# alimentare_no_ac.net
KiCad netlist of a schematic drawn in EAGLE
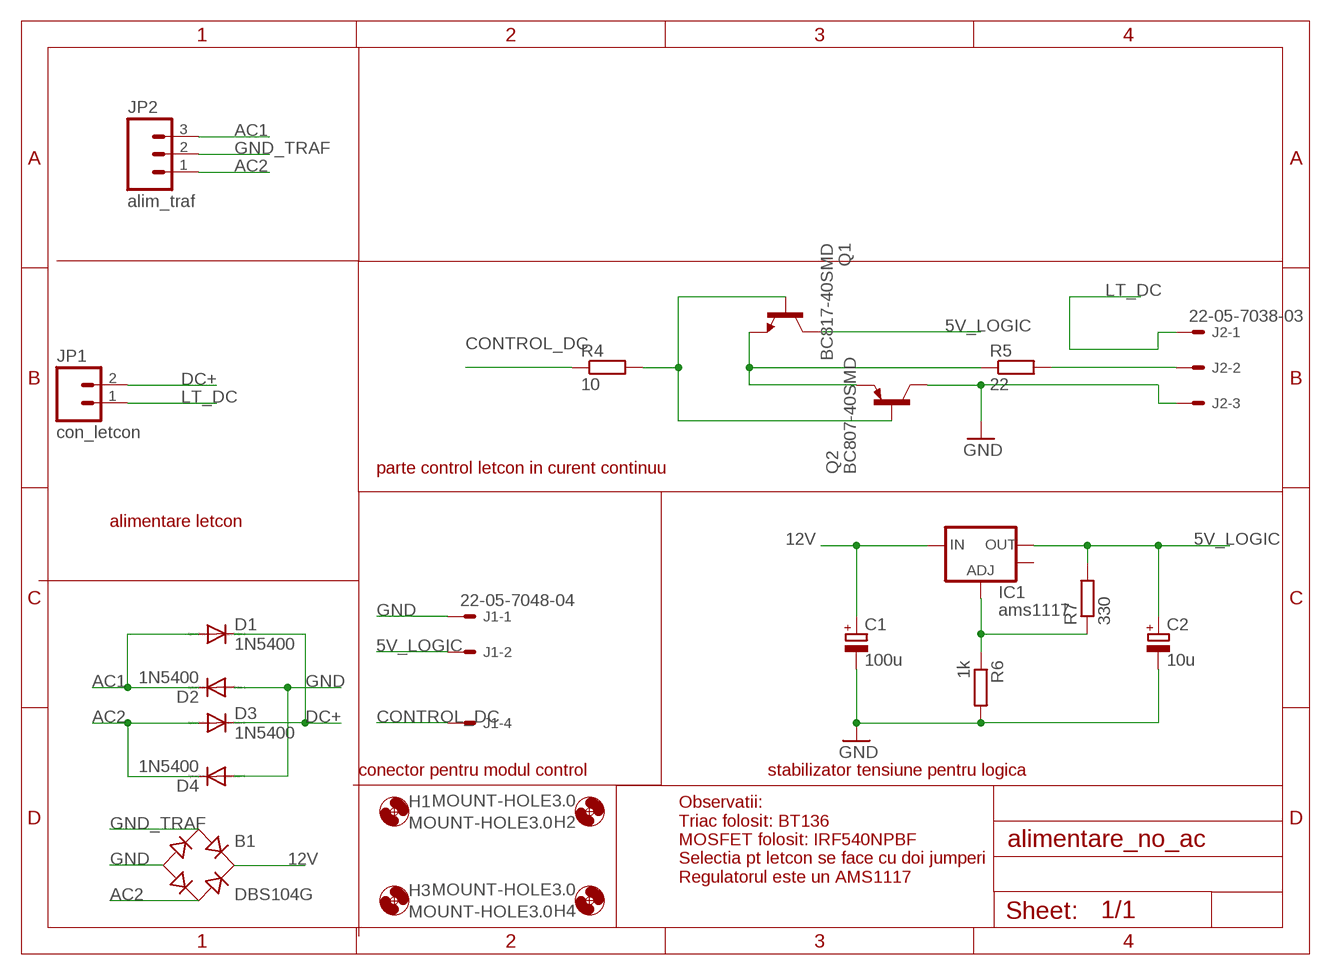
[diagram p0: schematic, sheet 1]

(export (version "E")
  (design (tool "Eeschema 10.0.6"))
  (components
    (comp (ref "B1")
      (value "DBS104G")
      (footprint "eagle-import:DBS")
      (libsource (lib "eagle-import") (part "DB?GS104"))
    )
    (comp (ref "C1")
      (value "100u")
      (footprint "eagle-import:E2,5-6E")
      (libsource (lib "eagle-import") (part "CPOL-EUE2,5-6E"))
    )
    (comp (ref "C2")
      (value "10u")
      (footprint "eagle-import:E2,5-6E")
      (libsource (lib "eagle-import") (part "CPOL-EUE2,5-6E"))
    )
    (comp (ref "D1")
      (value "1N5400")
      (footprint "eagle-import:DO201-15")
      (libsource (lib "eagle-import") (part "1N5400"))
    )
    (comp (ref "D2")
      (value "1N5400")
      (footprint "eagle-import:DO201-15")
      (libsource (lib "eagle-import") (part "1N5400"))
    )
    (comp (ref "D3")
      (value "1N5400")
      (footprint "eagle-import:DO201-15")
      (libsource (lib "eagle-import") (part "1N5400"))
    )
    (comp (ref "D4")
      (value "1N5400")
      (footprint "eagle-import:DO201-15")
      (libsource (lib "eagle-import") (part "1N5400"))
    )
    (comp (ref "H1")
      (value "MOUNT-HOLE3.0")
      (footprint "eagle-import:3,0")
      (libsource (lib "eagle-import") (part "MOUNT-HOLE3.0"))
    )
    (comp (ref "H2")
      (value "MOUNT-HOLE3.0")
      (footprint "eagle-import:3,0")
      (libsource (lib "eagle-import") (part "MOUNT-HOLE3.0"))
    )
    (comp (ref "H3")
      (value "MOUNT-HOLE3.0")
      (footprint "eagle-import:3,0")
      (libsource (lib "eagle-import") (part "MOUNT-HOLE3.0"))
    )
    (comp (ref "H4")
      (value "MOUNT-HOLE3.0")
      (footprint "eagle-import:3,0")
      (libsource (lib "eagle-import") (part "MOUNT-HOLE3.0"))
    )
    (comp (ref "IC1")
      (value "ams1117")
      (footprint "eagle-import:SOT223")
      (libsource (lib "eagle-import") (part "V_REG_LM1117SOT223"))
    )
    (comp (ref "J1")
      (value "22-05-7048-04")
      (footprint "eagle-import:7395-04")
      (libsource (lib "eagle-import") (part "22-?-0405-7048"))
    )
    (comp (ref "J2")
      (value "22-05-7038-03")
      (footprint "eagle-import:7395-03")
      (libsource (lib "eagle-import") (part "22-?-0305-7038"))
    )
    (comp (ref "JP1")
      (value "con_letcon")
      (footprint "eagle-import:SCREWTERMINAL-3.5MM-2")
      (libsource (lib "eagle-import") (part "M023.5MM"))
    )
    (comp (ref "JP2")
      (value "alim_traf")
      (footprint "eagle-import:SCREWTERMINAL-3.5MM-3")
      (libsource (lib "eagle-import") (part "M03SCREW"))
    )
    (comp (ref "Q1")
      (value "BC817-40SMD")
      (footprint "eagle-import:SOT23-BEC")
      (libsource (lib "eagle-import") (part "BC817SMD-40"))
    )
    (comp (ref "Q2")
      (value "BC807-40SMD")
      (footprint "eagle-import:SOT23-BEC")
      (libsource (lib "eagle-import") (part "BC807SMD-40"))
    )
    (comp (ref "R4")
      (value "10")
      (footprint "eagle-import:M1206")
      (libsource (lib "eagle-import") (part "R-EU_M1206"))
    )
    (comp (ref "R5")
      (value "22")
      (footprint "eagle-import:M1206")
      (libsource (lib "eagle-import") (part "R-EU_M1206"))
    )
    (comp (ref "R6")
      (value "1k")
      (footprint "eagle-import:M1206")
      (libsource (lib "eagle-import") (part "R-EU_M1206"))
    )
    (comp (ref "R7")
      (value "330")
      (footprint "eagle-import:M1206")
      (libsource (lib "eagle-import") (part "R-EU_M1206"))
    )
  )
  (nets
    (net (code "1") (name "/5V_LOGIC") (class "Default")
      (node (ref "C2") (pin "+") (pinfunction "+_+") (pintype "passive"))
      (node (ref "IC1") (pin "2") (pinfunction "OUT_2") (pintype "output"))
      (node (ref "J1") (pin "2") (pinfunction "S_2") (pintype "passive"))
      (node (ref "Q1") (pin "C") (pinfunction "C_C") (pintype "passive"))
      (node (ref "R7") (pin "2") (pinfunction "2_2") (pintype "passive"))
    )
    (net (code "2") (name "/12V") (class "Default")
      (node (ref "B1") (pin "+") (pinfunction "+_+") (pintype "passive"))
      (node (ref "C1") (pin "+") (pinfunction "+_+") (pintype "passive"))
      (node (ref "IC1") (pin "3") (pinfunction "IN_3") (pintype "input"))
    )
    (net (code "3") (name "/AC1") (class "Default")
      (node (ref "D1") (pin "A") (pinfunction "A_A") (pintype "passive"))
      (node (ref "D2") (pin "C") (pinfunction "C_C") (pintype "passive"))
      (node (ref "JP2") (pin "3") (pinfunction "3_3") (pintype "passive"))
    )
    (net (code "4") (name "/AC2") (class "Default")
      (node (ref "B1") (pin "AC2") (pinfunction "AC2_AC2") (pintype "passive"))
      (node (ref "D3") (pin "A") (pinfunction "A_A") (pintype "passive"))
      (node (ref "D4") (pin "C") (pinfunction "C_C") (pintype "passive"))
      (node (ref "JP2") (pin "1") (pinfunction "1_1") (pintype "passive"))
    )
    (net (code "5") (name "/CONTROL_DC") (class "Default")
      (node (ref "J1") (pin "4") (pinfunction "S_4") (pintype "passive"))
      (node (ref "R4") (pin "1") (pinfunction "1_1") (pintype "passive"))
    )
    (net (code "6") (name "/DC+") (class "Default")
      (node (ref "D1") (pin "C") (pinfunction "C_C") (pintype "passive"))
      (node (ref "D3") (pin "C") (pinfunction "C_C") (pintype "passive"))
      (node (ref "JP1") (pin "2") (pinfunction "2_2") (pintype "passive"))
    )
    (net (code "7") (name "/GND_TRAF") (class "Default")
      (node (ref "B1") (pin "AC1") (pinfunction "AC1_AC1") (pintype "passive"))
      (node (ref "JP2") (pin "2") (pinfunction "2_2") (pintype "passive"))
    )
    (net (code "8") (name "/LT_DC") (class "Default")
      (node (ref "J2") (pin "1") (pinfunction "S_1") (pintype "passive"))
      (node (ref "JP1") (pin "1") (pinfunction "1_1") (pintype "passive"))
    )
    (net (code "9") (name "GND") (class "Default")
      (node (ref "B1") (pin "-") (pinfunction "-_-") (pintype "passive"))
      (node (ref "C1") (pin "-") (pinfunction "-_-") (pintype "passive"))
      (node (ref "C2") (pin "-") (pinfunction "-_-") (pintype "passive"))
      (node (ref "D2") (pin "A") (pinfunction "A_A") (pintype "passive"))
      (node (ref "D4") (pin "A") (pinfunction "A_A") (pintype "passive"))
      (node (ref "J1") (pin "1") (pinfunction "S_1") (pintype "passive"))
      (node (ref "J2") (pin "3") (pinfunction "S_3") (pintype "passive"))
      (node (ref "Q2") (pin "C") (pinfunction "C_C") (pintype "passive"))
      (node (ref "R6") (pin "2") (pinfunction "2_2") (pintype "passive"))
    )
    (net (code "10") (name "Net-(IC1-ADJ)") (class "Default")
      (node (ref "IC1") (pin "1") (pinfunction "ADJ_1") (pintype "input"))
      (node (ref "R6") (pin "1") (pinfunction "1_1") (pintype "passive"))
      (node (ref "R7") (pin "1") (pinfunction "1_1") (pintype "passive"))
    )
    (net (code "11") (name "Net-(J2B-S)") (class "Default")
      (node (ref "J2") (pin "2") (pinfunction "S_2") (pintype "passive"))
      (node (ref "R5") (pin "2") (pinfunction "2_2") (pintype "passive"))
    )
    (net (code "12") (name "Net-(Q1-PadB)") (class "Default")
      (node (ref "Q1") (pin "B") (pinfunction "B_B") (pintype "passive"))
      (node (ref "Q2") (pin "B") (pinfunction "B_B") (pintype "passive"))
      (node (ref "R4") (pin "2") (pinfunction "2_2") (pintype "passive"))
    )
    (net (code "13") (name "Net-(Q1-PadE)") (class "Default")
      (node (ref "Q1") (pin "E") (pinfunction "E_E") (pintype "passive"))
      (node (ref "Q2") (pin "E") (pinfunction "E_E") (pintype "passive"))
      (node (ref "R5") (pin "1") (pinfunction "1_1") (pintype "passive"))
    )
    (net (code "14") (name "unconnected-(IC1-OUT-Pad4)") (class "Default")
      (node (ref "IC1") (pin "4") (pinfunction "OUT_4") (pintype "output"))
    )
  )
)
